# FilterTestBoard.net
KiCad netlist of a schematic drawn in EAGLE
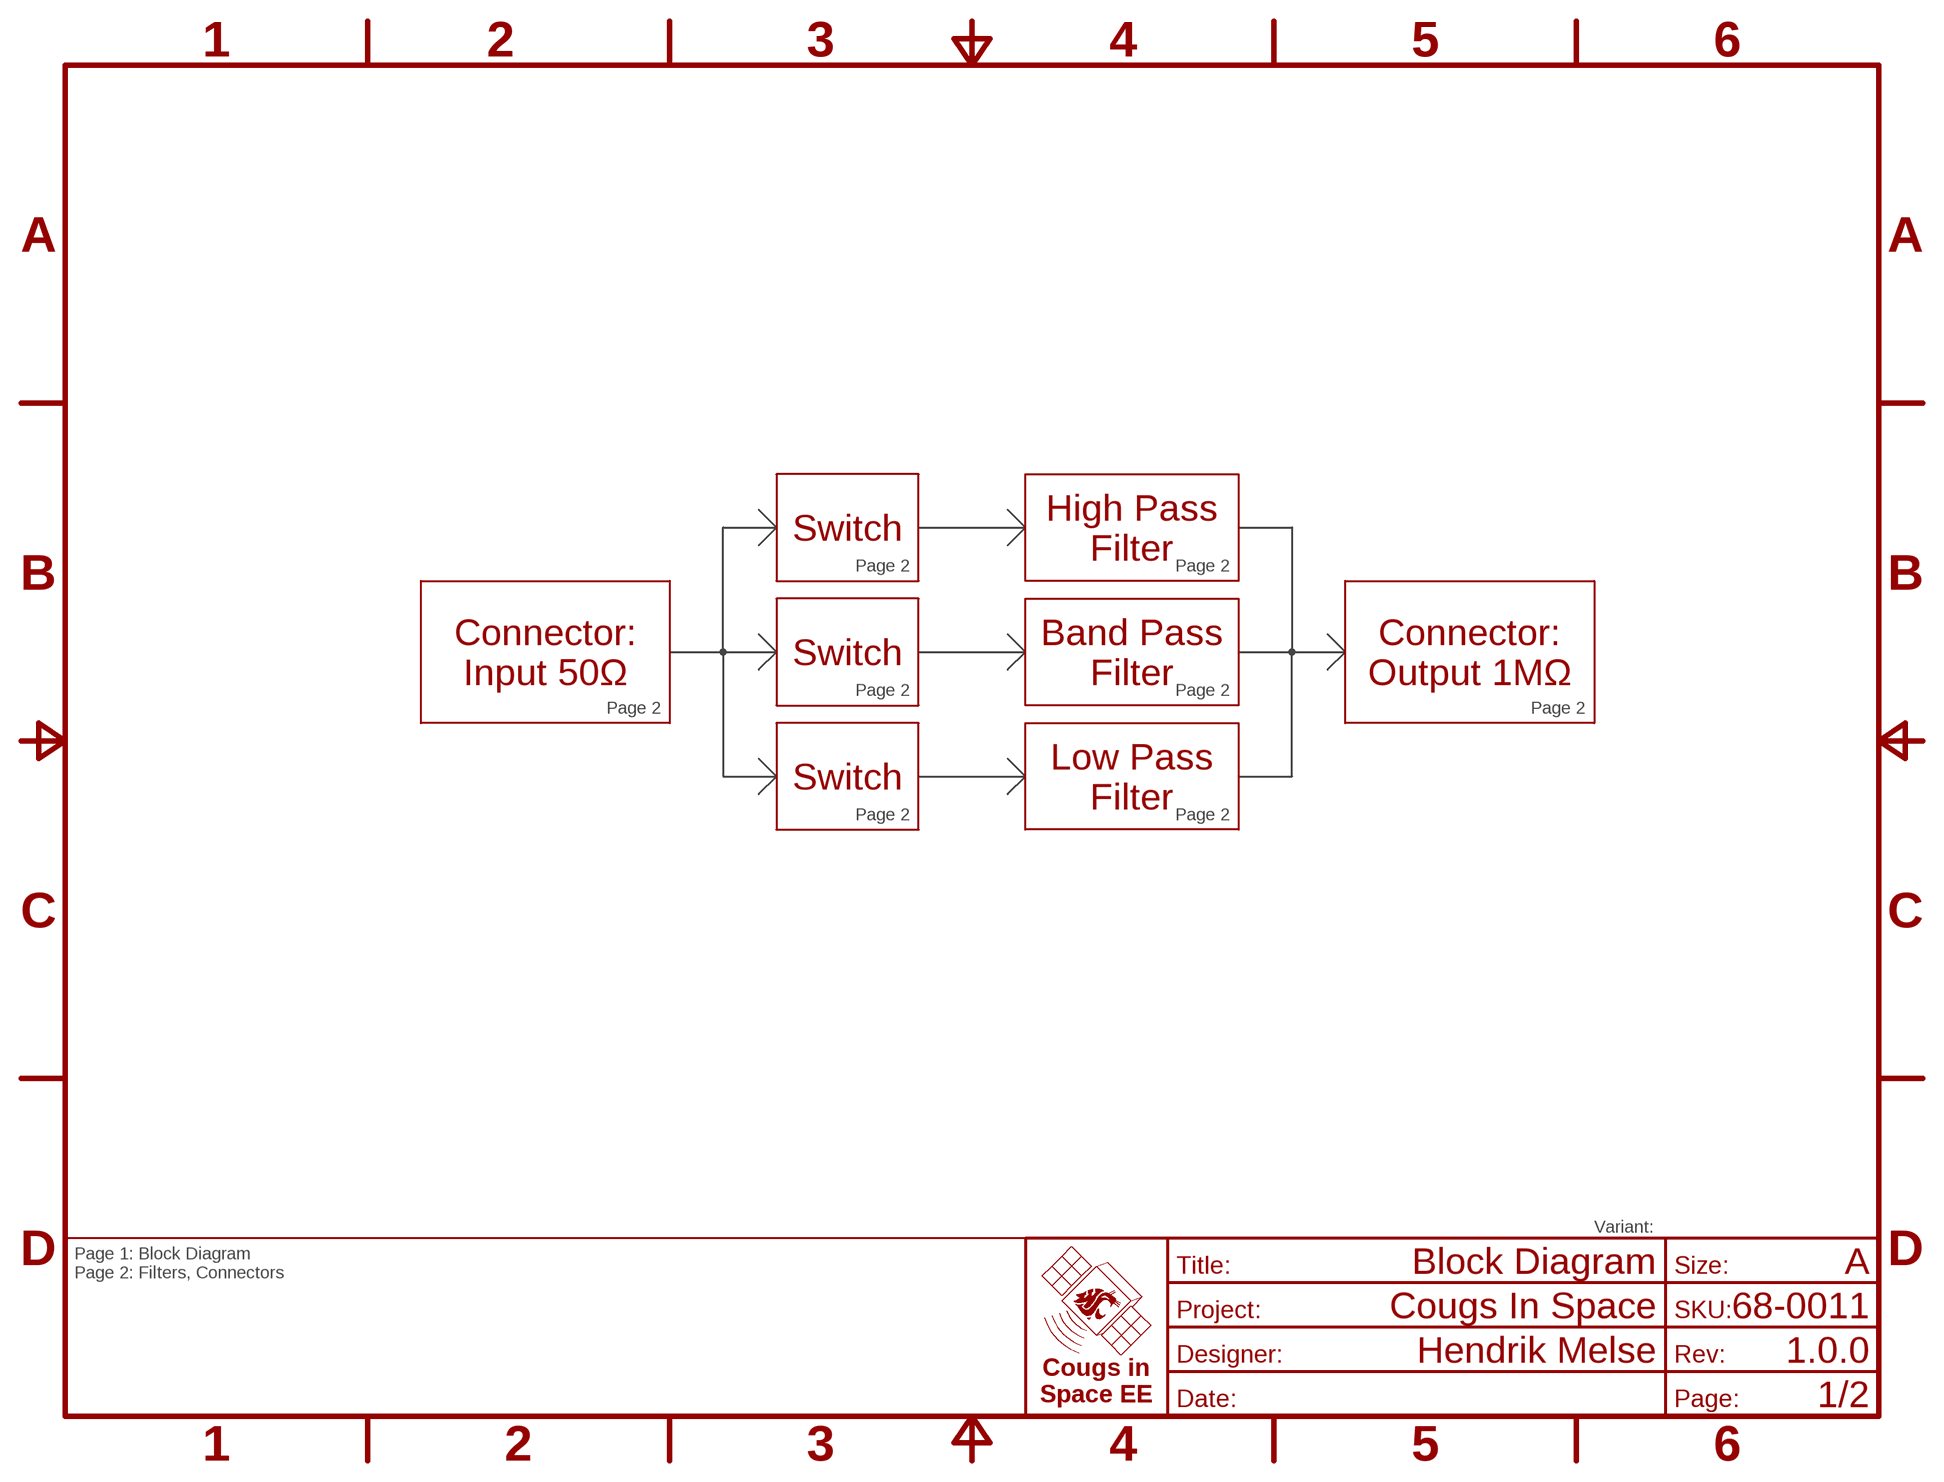
[diagram p0: schematic, sheet 1]
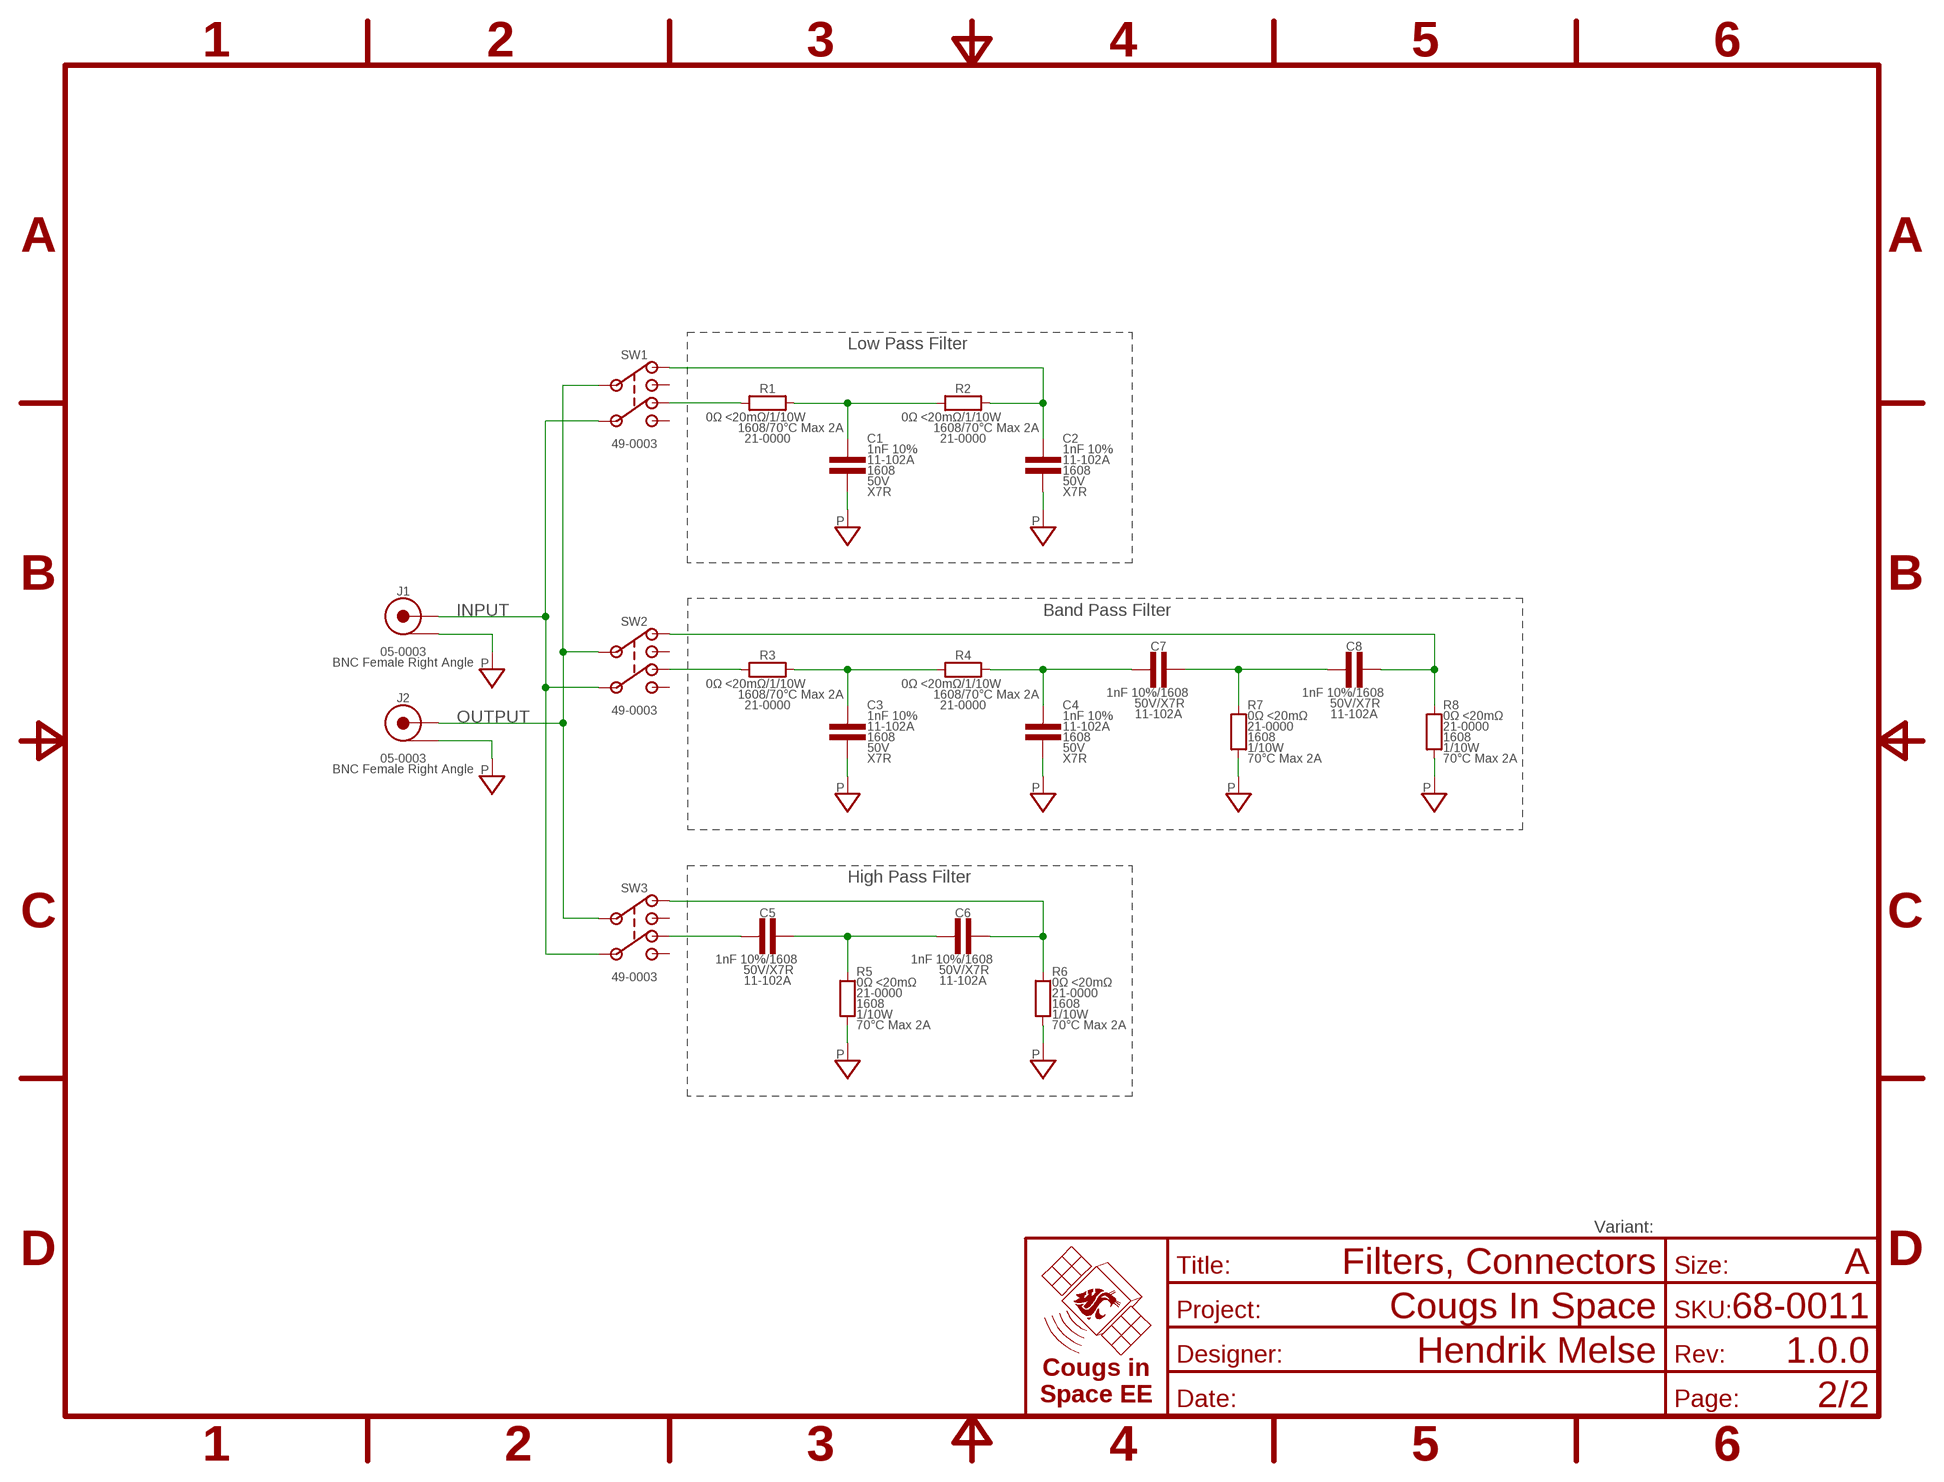
[diagram p1: schematic, sheet 2]

(export (version "E")
  (design (tool "Eeschema 10.0.6"))
  (components
    (comp (ref "C1")
      (value "1nF 10%")
      (footprint "eagle-import:1608")
      (fields
        (field (name "PACKAGE") "1608")
        (field (name "SKU") "11-102A")
        (field (name "TEMP") "X7R")
        (field (name "VOLTAGE") "50V")
      )
      (libsource (lib "eagle-import") (part "CAP-V-1608-1NF"))
    )
    (comp (ref "C2")
      (value "1nF 10%")
      (footprint "eagle-import:1608")
      (fields
        (field (name "PACKAGE") "1608")
        (field (name "SKU") "11-102A")
        (field (name "TEMP") "X7R")
        (field (name "VOLTAGE") "50V")
      )
      (libsource (lib "eagle-import") (part "CAP-V-1608-1NF"))
    )
    (comp (ref "C3")
      (value "1nF 10%")
      (footprint "eagle-import:1608")
      (fields
        (field (name "PACKAGE") "1608")
        (field (name "SKU") "11-102A")
        (field (name "TEMP") "X7R")
        (field (name "VOLTAGE") "50V")
      )
      (libsource (lib "eagle-import") (part "CAP-V-1608-1NF"))
    )
    (comp (ref "C4")
      (value "1nF 10%")
      (footprint "eagle-import:1608")
      (fields
        (field (name "PACKAGE") "1608")
        (field (name "SKU") "11-102A")
        (field (name "TEMP") "X7R")
        (field (name "VOLTAGE") "50V")
      )
      (libsource (lib "eagle-import") (part "CAP-V-1608-1NF"))
    )
    (comp (ref "C5")
      (value "1nF 10%")
      (footprint "eagle-import:1608")
      (fields
        (field (name "PACKAGE") "1608")
        (field (name "SKU") "11-102A")
        (field (name "TEMP") "X7R")
        (field (name "VOLTAGE") "50V")
      )
      (libsource (lib "eagle-import") (part "CAP-H-1608-1NF"))
    )
    (comp (ref "C6")
      (value "1nF 10%")
      (footprint "eagle-import:1608")
      (fields
        (field (name "PACKAGE") "1608")
        (field (name "SKU") "11-102A")
        (field (name "TEMP") "X7R")
        (field (name "VOLTAGE") "50V")
      )
      (libsource (lib "eagle-import") (part "CAP-H-1608-1NF"))
    )
    (comp (ref "C7")
      (value "1nF 10%")
      (footprint "eagle-import:1608")
      (fields
        (field (name "PACKAGE") "1608")
        (field (name "SKU") "11-102A")
        (field (name "TEMP") "X7R")
        (field (name "VOLTAGE") "50V")
      )
      (libsource (lib "eagle-import") (part "CAP-H-1608-1NF"))
    )
    (comp (ref "C8")
      (value "1nF 10%")
      (footprint "eagle-import:1608")
      (fields
        (field (name "PACKAGE") "1608")
        (field (name "SKU") "11-102A")
        (field (name "TEMP") "X7R")
        (field (name "VOLTAGE") "50V")
      )
      (libsource (lib "eagle-import") (part "CAP-H-1608-1NF"))
    )
    (comp (ref "J1")
      (value "COAX-BNC-T-R")
      (footprint "eagle-import:BNC-T-R")
      (fields (field (name "SKU") "05-0003") (field (name "PACKAGE") "BNC Female Right Angle"))
      (libsource (lib "eagle-import") (part "COAX-BNC-T-R"))
    )
    (comp (ref "J2")
      (value "COAX-BNC-T-R")
      (footprint "eagle-import:BNC-T-R")
      (fields (field (name "SKU") "05-0003") (field (name "PACKAGE") "BNC Female Right Angle"))
      (libsource (lib "eagle-import") (part "COAX-BNC-T-R"))
    )
    (comp (ref "R1")
      (value "0Ω <20mΩ")
      (footprint "eagle-import:1608")
      (fields
        (field (name "PACKAGE") "1608")
        (field (name "POWER") "1/10W")
        (field (name "SKU") "21-0000")
        (field (name "TEMP") "70°C Max 2A")
      )
      (libsource (lib "eagle-import") (part "RES-H-1608-0"))
    )
    (comp (ref "R2")
      (value "0Ω <20mΩ")
      (footprint "eagle-import:1608")
      (fields
        (field (name "PACKAGE") "1608")
        (field (name "POWER") "1/10W")
        (field (name "SKU") "21-0000")
        (field (name "TEMP") "70°C Max 2A")
      )
      (libsource (lib "eagle-import") (part "RES-H-1608-0"))
    )
    (comp (ref "R3")
      (value "0Ω <20mΩ")
      (footprint "eagle-import:1608")
      (fields
        (field (name "PACKAGE") "1608")
        (field (name "POWER") "1/10W")
        (field (name "SKU") "21-0000")
        (field (name "TEMP") "70°C Max 2A")
      )
      (libsource (lib "eagle-import") (part "RES-H-1608-0"))
    )
    (comp (ref "R4")
      (value "0Ω <20mΩ")
      (footprint "eagle-import:1608")
      (fields
        (field (name "PACKAGE") "1608")
        (field (name "POWER") "1/10W")
        (field (name "SKU") "21-0000")
        (field (name "TEMP") "70°C Max 2A")
      )
      (libsource (lib "eagle-import") (part "RES-H-1608-0"))
    )
    (comp (ref "R5")
      (value "0Ω <20mΩ")
      (footprint "eagle-import:1608")
      (fields
        (field (name "PACKAGE") "1608")
        (field (name "POWER") "1/10W")
        (field (name "SKU") "21-0000")
        (field (name "TEMP") "70°C Max 2A")
      )
      (libsource (lib "eagle-import") (part "RES-V-1608-0"))
    )
    (comp (ref "R6")
      (value "0Ω <20mΩ")
      (footprint "eagle-import:1608")
      (fields
        (field (name "PACKAGE") "1608")
        (field (name "POWER") "1/10W")
        (field (name "SKU") "21-0000")
        (field (name "TEMP") "70°C Max 2A")
      )
      (libsource (lib "eagle-import") (part "RES-V-1608-0"))
    )
    (comp (ref "R7")
      (value "0Ω <20mΩ")
      (footprint "eagle-import:1608")
      (fields
        (field (name "PACKAGE") "1608")
        (field (name "POWER") "1/10W")
        (field (name "SKU") "21-0000")
        (field (name "TEMP") "70°C Max 2A")
      )
      (libsource (lib "eagle-import") (part "RES-V-1608-0"))
    )
    (comp (ref "R8")
      (value "0Ω <20mΩ")
      (footprint "eagle-import:1608")
      (fields
        (field (name "PACKAGE") "1608")
        (field (name "POWER") "1/10W")
        (field (name "SKU") "21-0000")
        (field (name "TEMP") "70°C Max 2A")
      )
      (libsource (lib "eagle-import") (part "RES-V-1608-0"))
    )
    (comp (ref "SW1")
      (value "SWITCH-DPDT-100DP1T1B1M2QE")
      (footprint "eagle-import:100DP1T1B1M2QE")
      (fields (field (name "SKU") "49-0003"))
      (libsource (lib "eagle-import") (part "SWITCH-DPDT-100DP1T1B1M2QE"))
    )
    (comp (ref "SW2")
      (value "SWITCH-DPDT-100DP1T1B1M2QE")
      (footprint "eagle-import:100DP1T1B1M2QE")
      (fields (field (name "SKU") "49-0003"))
      (libsource (lib "eagle-import") (part "SWITCH-DPDT-100DP1T1B1M2QE"))
    )
    (comp (ref "SW3")
      (value "SWITCH-DPDT-100DP1T1B1M2QE")
      (footprint "eagle-import:100DP1T1B1M2QE")
      (fields (field (name "SKU") "49-0003"))
      (libsource (lib "eagle-import") (part "SWITCH-DPDT-100DP1T1B1M2QE"))
    )
  )
  (nets
    (net (code "1") (name "INPUT") (class "Default")
      (node (ref "J1") (pin "CENTER") (pinfunction "CENTER_CENTER") (pintype "bidirectional"))
      (node (ref "SW1") (pin "COM-B") (pinfunction "COM-B_COM-B") (pintype "passive"))
      (node (ref "SW2") (pin "COM-B") (pinfunction "COM-B_COM-B") (pintype "passive"))
      (node (ref "SW3") (pin "COM-B") (pinfunction "COM-B_COM-B") (pintype "passive"))
    )
    (net (code "2") (name "Net-(C1-Pad1)") (class "Default")
      (node (ref "C1") (pin "1") (pinfunction "1_1") (pintype "passive"))
      (node (ref "R1") (pin "2") (pinfunction "2_2") (pintype "passive"))
      (node (ref "R2") (pin "1") (pinfunction "1_1") (pintype "passive"))
    )
    (net (code "3") (name "Net-(C2-Pad1)") (class "Default")
      (node (ref "C2") (pin "1") (pinfunction "1_1") (pintype "passive"))
      (node (ref "R2") (pin "2") (pinfunction "2_2") (pintype "passive"))
      (node (ref "SW1") (pin "1-A") (pinfunction "1-A_1-A") (pintype "passive"))
    )
    (net (code "4") (name "Net-(C3-Pad1)") (class "Default")
      (node (ref "C3") (pin "1") (pinfunction "1_1") (pintype "passive"))
      (node (ref "R3") (pin "2") (pinfunction "2_2") (pintype "passive"))
      (node (ref "R4") (pin "1") (pinfunction "1_1") (pintype "passive"))
    )
    (net (code "5") (name "Net-(C4-Pad1)") (class "Default")
      (node (ref "C4") (pin "1") (pinfunction "1_1") (pintype "passive"))
      (node (ref "C7") (pin "1") (pinfunction "1_1") (pintype "passive"))
      (node (ref "R4") (pin "2") (pinfunction "2_2") (pintype "passive"))
    )
    (net (code "6") (name "Net-(C5-Pad1)") (class "Default")
      (node (ref "C5") (pin "1") (pinfunction "1_1") (pintype "passive"))
      (node (ref "SW3") (pin "1-B") (pinfunction "1-B_1-B") (pintype "passive"))
    )
    (net (code "7") (name "Net-(C5-Pad2)") (class "Default")
      (node (ref "C5") (pin "2") (pinfunction "2_2") (pintype "passive"))
      (node (ref "C6") (pin "1") (pinfunction "1_1") (pintype "passive"))
      (node (ref "R5") (pin "2") (pinfunction "2_2") (pintype "passive"))
    )
    (net (code "8") (name "Net-(C6-Pad2)") (class "Default")
      (node (ref "C6") (pin "2") (pinfunction "2_2") (pintype "passive"))
      (node (ref "R6") (pin "2") (pinfunction "2_2") (pintype "passive"))
      (node (ref "SW3") (pin "1-A") (pinfunction "1-A_1-A") (pintype "passive"))
    )
    (net (code "9") (name "Net-(C7-Pad2)") (class "Default")
      (node (ref "C7") (pin "2") (pinfunction "2_2") (pintype "passive"))
      (node (ref "C8") (pin "1") (pinfunction "1_1") (pintype "passive"))
      (node (ref "R7") (pin "2") (pinfunction "2_2") (pintype "passive"))
    )
    (net (code "10") (name "Net-(C8-Pad2)") (class "Default")
      (node (ref "C8") (pin "2") (pinfunction "2_2") (pintype "passive"))
      (node (ref "R8") (pin "2") (pinfunction "2_2") (pintype "passive"))
      (node (ref "SW2") (pin "1-A") (pinfunction "1-A_1-A") (pintype "passive"))
    )
    (net (code "11") (name "Net-(R1-Pad1)") (class "Default")
      (node (ref "R1") (pin "1") (pinfunction "1_1") (pintype "passive"))
      (node (ref "SW1") (pin "1-B") (pinfunction "1-B_1-B") (pintype "passive"))
    )
    (net (code "12") (name "Net-(R3-Pad1)") (class "Default")
      (node (ref "R3") (pin "1") (pinfunction "1_1") (pintype "passive"))
      (node (ref "SW2") (pin "1-B") (pinfunction "1-B_1-B") (pintype "passive"))
    )
    (net (code "13") (name "OUTPUT") (class "Default")
      (node (ref "J2") (pin "CENTER") (pinfunction "CENTER_CENTER") (pintype "bidirectional"))
      (node (ref "SW1") (pin "COM-A") (pinfunction "COM-A_COM-A") (pintype "passive"))
      (node (ref "SW2") (pin "COM-A") (pinfunction "COM-A_COM-A") (pintype "passive"))
      (node (ref "SW3") (pin "COM-A") (pinfunction "COM-A_COM-A") (pintype "passive"))
    )
    (net (code "14") (name "PGND") (class "Default")
      (node (ref "C1") (pin "2") (pinfunction "2_2") (pintype "passive"))
      (node (ref "C2") (pin "2") (pinfunction "2_2") (pintype "passive"))
      (node (ref "C3") (pin "2") (pinfunction "2_2") (pintype "passive"))
      (node (ref "C4") (pin "2") (pinfunction "2_2") (pintype "passive"))
      (node (ref "J1") (pin "SHIELD") (pinfunction "SHIELD_SHIELD") (pintype "bidirectional"))
      (node (ref "J2") (pin "SHIELD") (pinfunction "SHIELD_SHIELD") (pintype "bidirectional"))
      (node (ref "R5") (pin "1") (pinfunction "1_1") (pintype "passive"))
      (node (ref "R6") (pin "1") (pinfunction "1_1") (pintype "passive"))
      (node (ref "R7") (pin "1") (pinfunction "1_1") (pintype "passive"))
      (node (ref "R8") (pin "1") (pinfunction "1_1") (pintype "passive"))
    )
    (net (code "15") (name "unconnected-(SW1-Pad2-A)") (class "Default")
      (node (ref "SW1") (pin "2-A") (pinfunction "2-A_2-A") (pintype "passive"))
    )
    (net (code "16") (name "unconnected-(SW1-Pad2-B)") (class "Default")
      (node (ref "SW1") (pin "2-B") (pinfunction "2-B_2-B") (pintype "passive"))
    )
    (net (code "17") (name "unconnected-(SW2-Pad2-A)") (class "Default")
      (node (ref "SW2") (pin "2-A") (pinfunction "2-A_2-A") (pintype "passive"))
    )
    (net (code "18") (name "unconnected-(SW2-Pad2-B)") (class "Default")
      (node (ref "SW2") (pin "2-B") (pinfunction "2-B_2-B") (pintype "passive"))
    )
    (net (code "19") (name "unconnected-(SW3-Pad2-A)") (class "Default")
      (node (ref "SW3") (pin "2-A") (pinfunction "2-A_2-A") (pintype "passive"))
    )
    (net (code "20") (name "unconnected-(SW3-Pad2-B)") (class "Default")
      (node (ref "SW3") (pin "2-B") (pinfunction "2-B_2-B") (pintype "passive"))
    )
  )
)
